# Auxiliary.net
KiCad netlist of a schematic drawn in Altium Designer
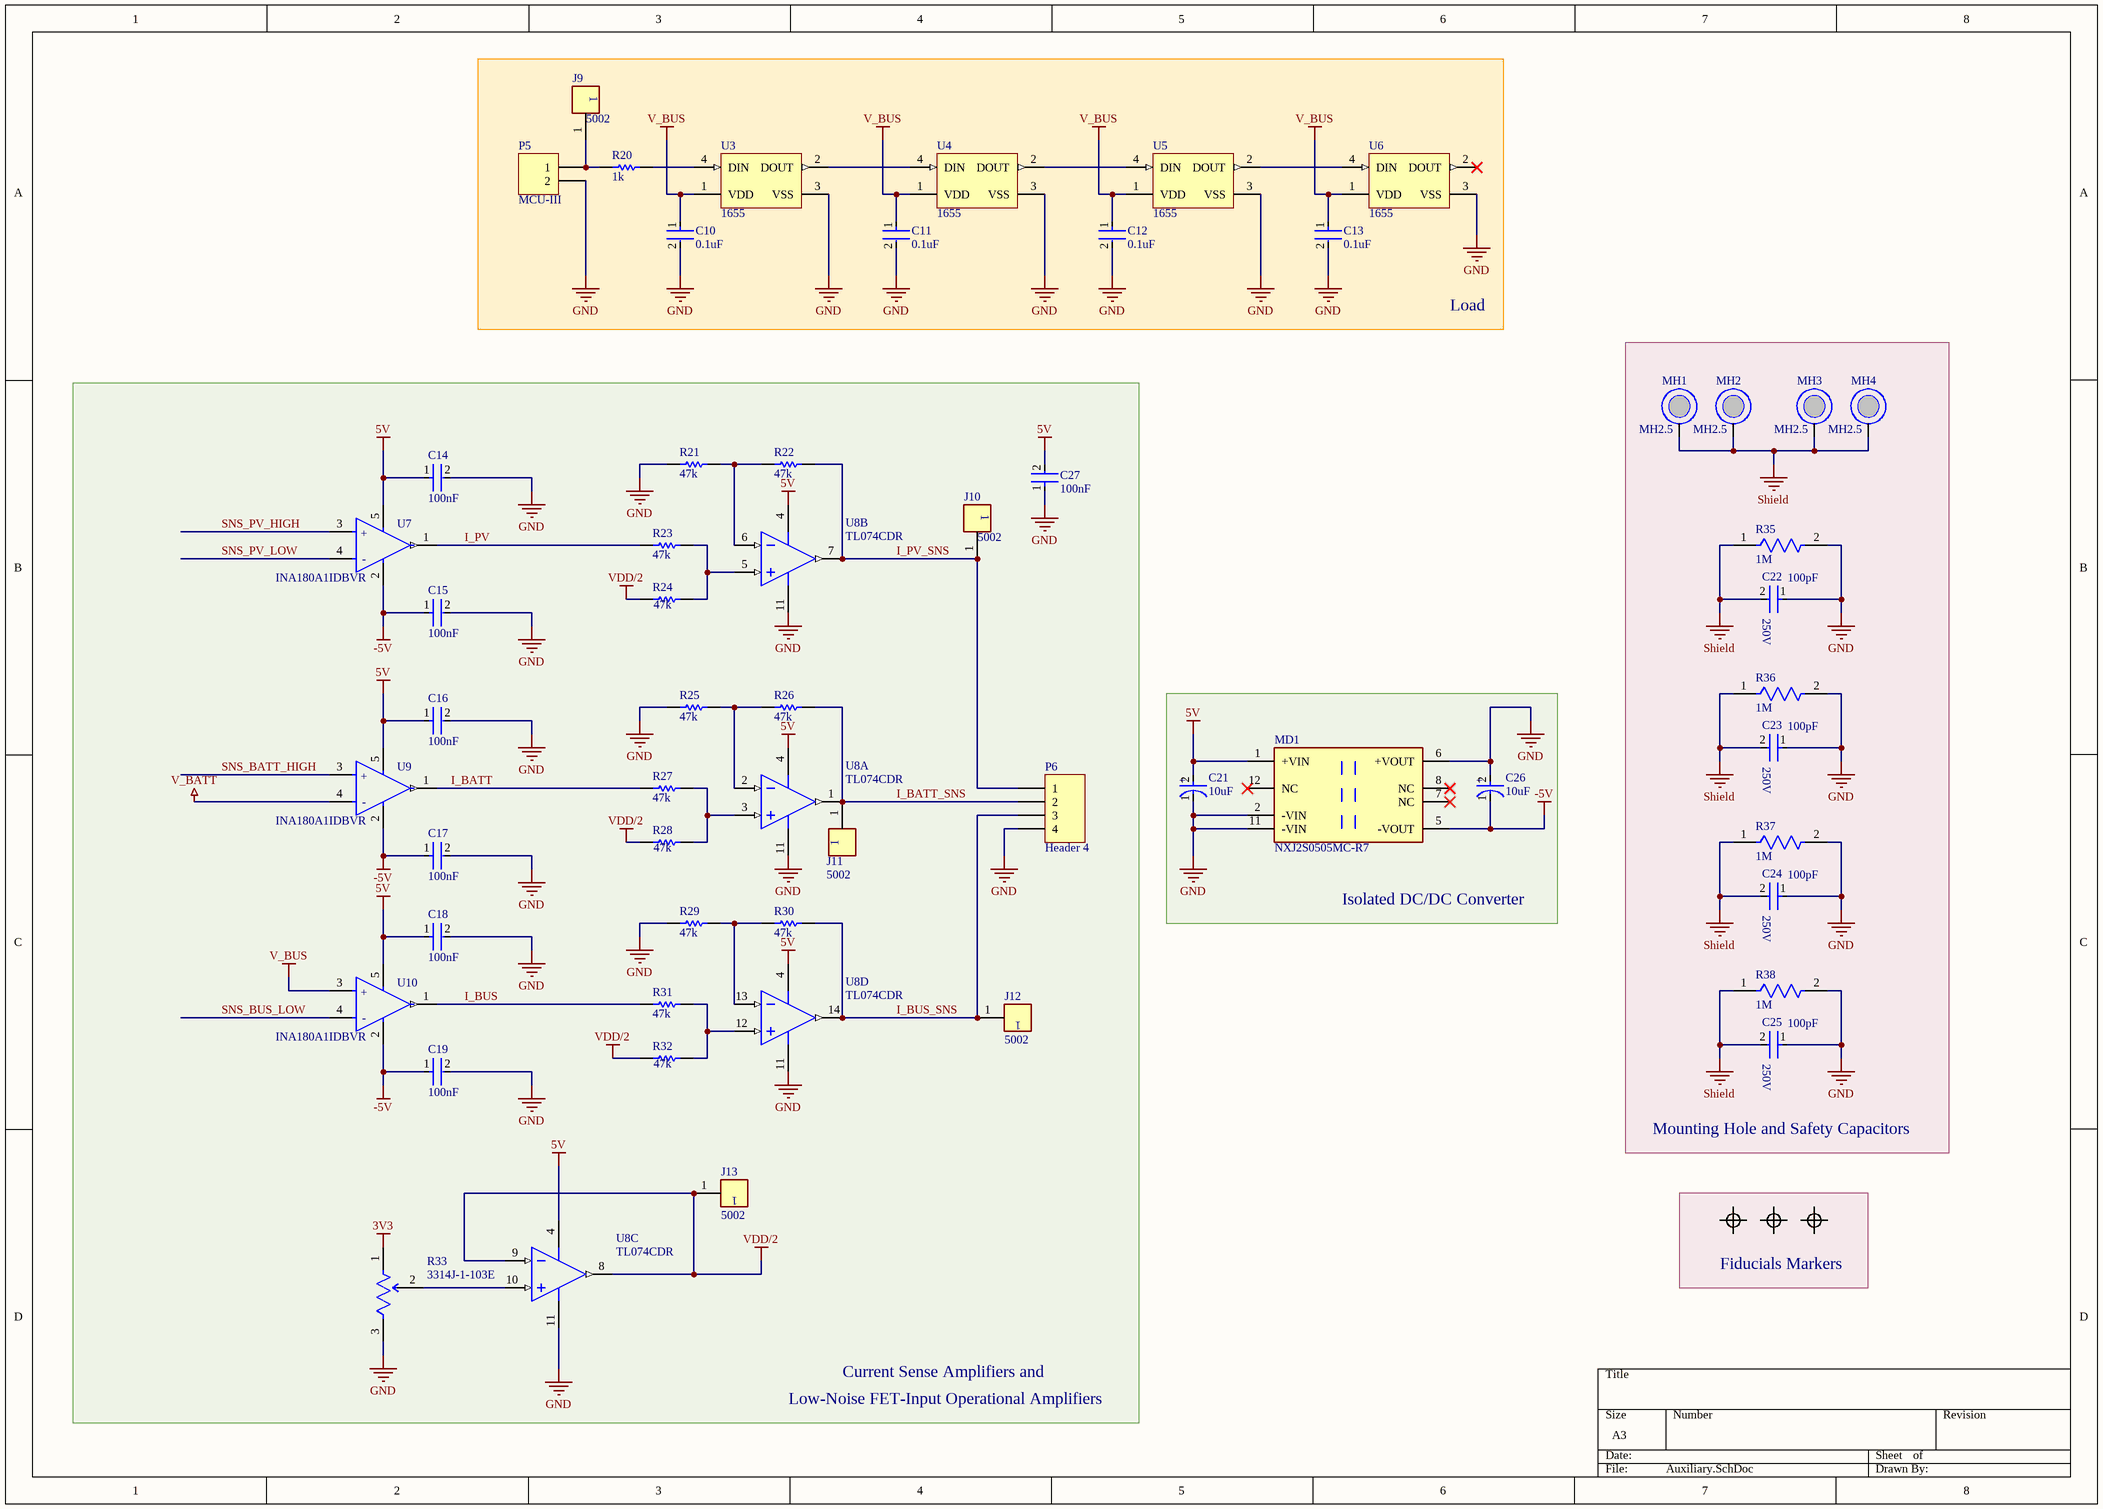
[diagram p0: Auxiliary.SchDoc]

(export (version "E")
  (design (tool "Eeschema 10.0.6"))
  (components
    (comp (ref "C10")
      (value "0.1uF")
      (footprint "FP-GRM155-0_05-MFG")
      (description "CAP CER 0.1UF 16V X7R 0402")
      (fields (field (name "TOLERANCE") "5%") (field (name "VOLTAGE") "16V"))
      (libsource (lib "Altium Content Vault") (part "02cd4be3c70576c341d710602a673aa"))
    )
    (comp (ref "C11")
      (value "0.1uF")
      (footprint "FP-GRM155-0_05-MFG")
      (description "CAP CER 0.1UF 16V X7R 0402")
      (fields (field (name "TOLERANCE") "5%") (field (name "VOLTAGE") "16V"))
      (libsource (lib "Altium Content Vault") (part "02cd4be3c70576c341d710602a673aa"))
    )
    (comp (ref "C12")
      (value "0.1uF")
      (footprint "FP-GRM155-0_05-MFG")
      (description "CAP CER 0.1UF 16V X7R 0402")
      (fields (field (name "TOLERANCE") "5%") (field (name "VOLTAGE") "16V"))
      (libsource (lib "Altium Content Vault") (part "02cd4be3c70576c341d710602a673aa"))
    )
    (comp (ref "C13")
      (value "0.1uF")
      (footprint "FP-GRM155-0_05-MFG")
      (description "CAP CER 0.1UF 16V X7R 0402")
      (fields (field (name "TOLERANCE") "5%") (field (name "VOLTAGE") "16V"))
      (libsource (lib "Altium Content Vault") (part "02cd4be3c70576c341d710602a673aa"))
    )
    (comp (ref "C14")
      (value "100nF")
      (footprint "FP-CGA3E-0_3-0_1-IPC_A")
      (description "Cap Ceramic 100nF 50V X7R 10% Pad SMD 0603 +125°C Automotive T/R")
      (fields (field (name "TOLERANCE") "10%") (field (name "VOLTAGE") "50V"))
      (libsource (lib "Altium Content Vault") (part "b4654b650e69147ec39a6b967a45e02"))
    )
    (comp (ref "C15")
      (value "100nF")
      (footprint "FP-CGA3E-0_3-0_1-IPC_A")
      (description "Cap Ceramic 100nF 50V X7R 10% Pad SMD 0603 +125°C Automotive T/R")
      (fields (field (name "TOLERANCE") "10%") (field (name "VOLTAGE") "50V"))
      (libsource (lib "Altium Content Vault") (part "b4654b650e69147ec39a6b967a45e02"))
    )
    (comp (ref "C16")
      (value "100nF")
      (footprint "FP-CGA3E-0_3-0_1-IPC_A")
      (description "Cap Ceramic 100nF 50V X7R 10% Pad SMD 0603 +125°C Automotive T/R")
      (fields (field (name "TOLERANCE") "10%") (field (name "VOLTAGE") "50V"))
      (libsource (lib "Altium Content Vault") (part "b4654b650e69147ec39a6b967a45e02"))
    )
    (comp (ref "C17")
      (value "100nF")
      (footprint "FP-CGA3E-0_3-0_1-IPC_A")
      (description "Cap Ceramic 100nF 50V X7R 10% Pad SMD 0603 +125°C Automotive T/R")
      (fields (field (name "TOLERANCE") "10%") (field (name "VOLTAGE") "50V"))
      (libsource (lib "Altium Content Vault") (part "b4654b650e69147ec39a6b967a45e02"))
    )
    (comp (ref "C18")
      (value "100nF")
      (footprint "FP-CGA3E-0_3-0_1-IPC_A")
      (description "Cap Ceramic 100nF 50V X7R 10% Pad SMD 0603 +125°C Automotive T/R")
      (fields (field (name "TOLERANCE") "10%") (field (name "VOLTAGE") "50V"))
      (libsource (lib "Altium Content Vault") (part "b4654b650e69147ec39a6b967a45e02"))
    )
    (comp (ref "C19")
      (value "100nF")
      (footprint "FP-CGA3E-0_3-0_1-IPC_A")
      (description "Cap Ceramic 100nF 50V X7R 10% Pad SMD 0603 +125°C Automotive T/R")
      (fields (field (name "TOLERANCE") "10%") (field (name "VOLTAGE") "50V"))
      (libsource (lib "Altium Content Vault") (part "b4654b650e69147ec39a6b967a45e02"))
    )
    (comp (ref "C21")
      (value "10uF")
      (footprint "FP-T491C106K016AT-MFG")
      (description "CAP TANT 10UF 10% 16V 2312")
      (fields (field (name "VOLTAGE") "16V") (field (name "TOLERANCE") "10%"))
      (libsource (lib "Altium Content Vault") (part "a00bbbee19879c290e62620ae7e47b1"))
    )
    (comp (ref "C22")
      (value "100pF")
      (footprint "FP-GA342Q-0_3-e0_3_1_15-IPC_C")
      (description "100pF ±10%  250VAC Ceramic Capacitor X7R 1808 (4520 Metric)")
      (fields (field (name "VOLTAGE") "250V") (field (name "TOLERANCE") "10%"))
      (libsource (lib "Altium Content Vault") (part "ee02319fe6c27a0cbee94bf8aee89f2"))
    )
    (comp (ref "C23")
      (value "100pF")
      (footprint "FP-GA342Q-0_3-e0_3_1_15-IPC_C")
      (description "100pF ±10%  250VAC Ceramic Capacitor X7R 1808 (4520 Metric)")
      (fields (field (name "VOLTAGE") "250V") (field (name "TOLERANCE") "10%"))
      (libsource (lib "Altium Content Vault") (part "ee02319fe6c27a0cbee94bf8aee89f2"))
    )
    (comp (ref "C24")
      (value "100pF")
      (footprint "FP-GA342Q-0_3-e0_3_1_15-IPC_C")
      (description "100pF ±10%  250VAC Ceramic Capacitor X7R 1808 (4520 Metric)")
      (fields (field (name "VOLTAGE") "250V") (field (name "TOLERANCE") "10%"))
      (libsource (lib "Altium Content Vault") (part "ee02319fe6c27a0cbee94bf8aee89f2"))
    )
    (comp (ref "C25")
      (value "100pF")
      (footprint "FP-GA342Q-0_3-e0_3_1_15-IPC_C")
      (description "100pF ±10%  250VAC Ceramic Capacitor X7R 1808 (4520 Metric)")
      (fields (field (name "VOLTAGE") "250V") (field (name "TOLERANCE") "10%"))
      (libsource (lib "Altium Content Vault") (part "ee02319fe6c27a0cbee94bf8aee89f2"))
    )
    (comp (ref "C26")
      (value "10uF")
      (footprint "FP-T491C106K016AT-MFG")
      (description "CAP TANT 10UF 10% 16V 2312")
      (fields (field (name "VOLTAGE") "16V") (field (name "TOLERANCE") "10%"))
      (libsource (lib "Altium Content Vault") (part "a00bbbee19879c290e62620ae7e47b1"))
    )
    (comp (ref "C27")
      (value "100nF")
      (footprint "FP-CGA3E-0_3-0_1-IPC_A")
      (description "Cap Ceramic 100nF 50V X7R 10% Pad SMD 0603 +125°C Automotive T/R")
      (fields (field (name "TOLERANCE") "10%") (field (name "VOLTAGE") "50V"))
      (libsource (lib "Altium Content Vault") (part "b4654b650e69147ec39a6b967a45e02"))
    )
    (comp (ref "F1")
      (value "FIDUCIAL")
      (footprint "FIDUCIAL")
      (libsource (lib "LUCRARE_LICENTA_SCHEMATIC") (part "FIDUCIAL"))
    )
    (comp (ref "F2")
      (value "FIDUCIAL")
      (footprint "FIDUCIAL")
      (libsource (lib "LUCRARE_LICENTA_SCHEMATIC") (part "FIDUCIAL"))
    )
    (comp (ref "F3")
      (value "FIDUCIAL")
      (footprint "FIDUCIAL")
      (libsource (lib "LUCRARE_LICENTA_SCHEMATIC") (part "FIDUCIAL"))
    )
    (comp (ref "J9")
      (value "5002")
      (footprint "FP-5002-MFG")
      (description "PC TEST POINT MINIATURE WHITE")
      (libsource (lib "") (part "1e4615820a309e3ce90f9e6d957b7fa_1"))
    )
    (comp (ref "J10")
      (value "5002")
      (footprint "FP-5002-MFG")
      (description "PC TEST POINT MINIATURE WHITE")
      (libsource (lib "") (part "1e4615820a309e3ce90f9e6d957b7fa_1"))
    )
    (comp (ref "J11")
      (value "5002")
      (footprint "FP-5002-MFG")
      (description "PC TEST POINT MINIATURE WHITE")
      (libsource (lib "") (part "1e4615820a309e3ce90f9e6d957b7fa_2"))
    )
    (comp (ref "J12")
      (value "5002")
      (footprint "FP-5002-MFG")
      (description "PC TEST POINT MINIATURE WHITE")
      (libsource (lib "Altium Content Vault") (part "1e4615820a309e3ce90f9e6d957b7fa"))
    )
    (comp (ref "J13")
      (value "5002")
      (footprint "FP-5002-MFG")
      (description "PC TEST POINT MINIATURE WHITE")
      (libsource (lib "Altium Content Vault") (part "1e4615820a309e3ce90f9e6d957b7fa"))
    )
    (comp (ref "MD1")
      (value "NXJ2S0505MC-R7")
      (footprint "FP-NXJ2SM-MFG")
      (description "DC DC CONVERTER 5V 2W")
      (libsource (lib "Altium Content Vault") (part "702c7546206b672000c29661061961a"))
    )
    (comp (ref "MH1")
      (value "MH2.5")
      (footprint "Mounting Hole")
      (libsource (lib "LUCRARE_LICENTA_SCHEMATIC") (part "Mounting Hole"))
    )
    (comp (ref "MH2")
      (value "MH2.5")
      (footprint "Mounting Hole")
      (libsource (lib "LUCRARE_LICENTA_SCHEMATIC") (part "Mounting Hole"))
    )
    (comp (ref "MH3")
      (value "MH2.5")
      (footprint "Mounting Hole")
      (libsource (lib "LUCRARE_LICENTA_SCHEMATIC") (part "Mounting Hole"))
    )
    (comp (ref "MH4")
      (value "MH2.5")
      (footprint "Mounting Hole")
      (libsource (lib "LUCRARE_LICENTA_SCHEMATIC") (part "Mounting Hole"))
    )
    (comp (ref "P5")
      (value "MCU-III")
      (footprint "HDR1X2")
      (description "Header, 2-Pin")
      (fields (field (name "PUBLISHER") "Altium Limited"))
      (libsource (lib "Miscellaneous Connectors") (part "Header 2"))
    )
    (comp (ref "P6")
      (value "Header 4")
      (footprint "HDR1X4")
      (description "Header, 4-Pin")
      (fields (field (name "PUBLISHER") "Altium Limited"))
      (libsource (lib "Miscellaneous Connectors") (part "Header 4"))
    )
    (comp (ref "R20")
      (value "1k")
      (footprint "RESC1608X55X30LL15T15")
      (fields (field (name "PART NUMBER") "ERJ-3EKF1001V") (field (name "MANUFACTURER") "Panasonic"))
      (libsource (lib "Altium Content Vault") (part "RES"))
    )
    (comp (ref "R21")
      (value "47k")
      (footprint "RESC1608X55X30NL15T15")
      (description "Chip Resistor, 47 KOhm, +/- 1%, 0.1 W, -55 to 155 degC, 0603 (1608 Metric), RoHS, Tape and Reel")
      (libsource (lib "Altium Content Vault") (part "RES-2"))
    )
    (comp (ref "R22")
      (value "47k")
      (footprint "RESC1608X55X30NL15T15")
      (description "Chip Resistor, 47 KOhm, +/- 1%, 0.1 W, -55 to 155 degC, 0603 (1608 Metric), RoHS, Tape and Reel")
      (libsource (lib "Altium Content Vault") (part "RES-2"))
    )
    (comp (ref "R23")
      (value "47k")
      (footprint "RESC1608X55X30NL15T15")
      (description "Chip Resistor, 47 KOhm, +/- 1%, 0.1 W, -55 to 155 degC, 0603 (1608 Metric), RoHS, Tape and Reel")
      (libsource (lib "Altium Content Vault") (part "RES-2"))
    )
    (comp (ref "R24")
      (value "47k")
      (footprint "RESC1608X55X30NL15T15")
      (description "Chip Resistor, 47 KOhm, +/- 1%, 0.1 W, -55 to 155 degC, 0603 (1608 Metric), RoHS, Tape and Reel")
      (libsource (lib "Altium Content Vault") (part "RES-2"))
    )
    (comp (ref "R25")
      (value "47k")
      (footprint "RESC1608X55X30NL15T15")
      (description "Chip Resistor, 47 KOhm, +/- 1%, 0.1 W, -55 to 155 degC, 0603 (1608 Metric), RoHS, Tape and Reel")
      (libsource (lib "Altium Content Vault") (part "RES-2"))
    )
    (comp (ref "R26")
      (value "47k")
      (footprint "RESC1608X55X30NL15T15")
      (description "Chip Resistor, 47 KOhm, +/- 1%, 0.1 W, -55 to 155 degC, 0603 (1608 Metric), RoHS, Tape and Reel")
      (libsource (lib "Altium Content Vault") (part "RES-2"))
    )
    (comp (ref "R27")
      (value "47k")
      (footprint "RESC1608X55X30NL15T15")
      (description "Chip Resistor, 47 KOhm, +/- 1%, 0.1 W, -55 to 155 degC, 0603 (1608 Metric), RoHS, Tape and Reel")
      (libsource (lib "Altium Content Vault") (part "RES-2"))
    )
    (comp (ref "R28")
      (value "47k")
      (footprint "RESC1608X55X30NL15T15")
      (description "Chip Resistor, 47 KOhm, +/- 1%, 0.1 W, -55 to 155 degC, 0603 (1608 Metric), RoHS, Tape and Reel")
      (libsource (lib "Altium Content Vault") (part "RES-2"))
    )
    (comp (ref "R29")
      (value "47k")
      (footprint "RESC1608X55X30NL15T15")
      (description "Chip Resistor, 47 KOhm, +/- 1%, 0.1 W, -55 to 155 degC, 0603 (1608 Metric), RoHS, Tape and Reel")
      (libsource (lib "Altium Content Vault") (part "RES-2"))
    )
    (comp (ref "R30")
      (value "47k")
      (footprint "RESC1608X55X30NL15T15")
      (description "Chip Resistor, 47 KOhm, +/- 1%, 0.1 W, -55 to 155 degC, 0603 (1608 Metric), RoHS, Tape and Reel")
      (libsource (lib "Altium Content Vault") (part "RES-2"))
    )
    (comp (ref "R31")
      (value "47k")
      (footprint "RESC1608X55X30NL15T15")
      (description "Chip Resistor, 47 KOhm, +/- 1%, 0.1 W, -55 to 155 degC, 0603 (1608 Metric), RoHS, Tape and Reel")
      (libsource (lib "Altium Content Vault") (part "RES-2"))
    )
    (comp (ref "R32")
      (value "47k")
      (footprint "RESC1608X55X30NL15T15")
      (description "Chip Resistor, 47 KOhm, +/- 1%, 0.1 W, -55 to 155 degC, 0603 (1608 Metric), RoHS, Tape and Reel")
      (libsource (lib "Altium Content Vault") (part "RES-2"))
    )
    (comp (ref "R33")
      (value "3314J-1-103E")
      (footprint "FP-3314J-1-MFG")
      (description "TRIMMER 10K OHM 0.25W J LEAD TOP")
      (libsource (lib "Altium Content Vault") (part "13357d81287629c2fd191d242cfa50c"))
    )
    (comp (ref "R35")
      (value "1M")
      (footprint "FP-CRCW0603C-e3-MFG")
      (description "RES 1M OHM 1% 1/10W 0603")
      (fields (field (name "TOLERANCE") "1%"))
      (libsource (lib "Altium Content Vault") (part "1029c3af85768c4190bb7ad29bc67b5"))
    )
    (comp (ref "R36")
      (value "1M")
      (footprint "FP-CRCW0603C-e3-MFG")
      (description "RES 1M OHM 1% 1/10W 0603")
      (fields (field (name "TOLERANCE") "1%"))
      (libsource (lib "Altium Content Vault") (part "1029c3af85768c4190bb7ad29bc67b5"))
    )
    (comp (ref "R37")
      (value "1M")
      (footprint "FP-CRCW0603C-e3-MFG")
      (description "RES 1M OHM 1% 1/10W 0603")
      (fields (field (name "TOLERANCE") "1%"))
      (libsource (lib "Altium Content Vault") (part "1029c3af85768c4190bb7ad29bc67b5"))
    )
    (comp (ref "R38")
      (value "1M")
      (footprint "FP-CRCW0603C-e3-MFG")
      (description "RES 1M OHM 1% 1/10W 0603")
      (fields (field (name "TOLERANCE") "1%"))
      (libsource (lib "Altium Content Vault") (part "1029c3af85768c4190bb7ad29bc67b5"))
    )
    (comp (ref "U3")
      (value "1655")
      (footprint "ADA-RGB-1655_V")
      (fields (field (name "MANUFACTURER") "Adafruit-Industries-LLC"))
      (libsource (lib "Altium Content Vault") (part "ADA-RGB-1655-4"))
    )
    (comp (ref "U4")
      (value "1655")
      (footprint "ADA-RGB-1655_V")
      (fields (field (name "MANUFACTURER") "Adafruit-Industries-LLC"))
      (libsource (lib "Altium Content Vault") (part "ADA-RGB-1655-4"))
    )
    (comp (ref "U5")
      (value "1655")
      (footprint "ADA-RGB-1655_V")
      (fields (field (name "MANUFACTURER") "Adafruit-Industries-LLC"))
      (libsource (lib "Altium Content Vault") (part "ADA-RGB-1655-4"))
    )
    (comp (ref "U6")
      (value "1655")
      (footprint "ADA-RGB-1655_V")
      (fields (field (name "MANUFACTURER") "Adafruit-Industries-LLC"))
      (libsource (lib "Altium Content Vault") (part "ADA-RGB-1655-4"))
    )
    (comp (ref "U7")
      (value "INA180A1IDBVR")
      (footprint "FP-DBV0005A-IPC_A")
      (description "IC CURR SENSE 1 CIRCUIT SOT23-5")
      (libsource (lib "Altium Content Vault") (part "0a55cf1a948ad01a3239aec1b7efad0"))
    )
    (comp (ref "U8")
      (value "TL074CDR")
      (footprint "D0014A_N")
      (fields (field (name "MANUFACTURER") "Texas Instruments"))
      (libsource (lib "Altium Content Vault") (part "TI-TLXX4X_MC3403-X14"))
    )
    (comp (ref "U9")
      (value "INA180A1IDBVR")
      (footprint "FP-DBV0005A-IPC_A")
      (description "IC CURR SENSE 1 CIRCUIT SOT23-5")
      (libsource (lib "Altium Content Vault") (part "0a55cf1a948ad01a3239aec1b7efad0"))
    )
    (comp (ref "U10")
      (value "INA180A1IDBVR")
      (footprint "FP-DBV0005A-IPC_A")
      (description "IC CURR SENSE 1 CIRCUIT SOT23-5")
      (libsource (lib "Altium Content Vault") (part "0a55cf1a948ad01a3239aec1b7efad0"))
    )
  )
  (nets
    (net (code "1") (name "-5V") (class "Default")
      (node (ref "C15") (pin "1") (pinfunction "1_1") (pintype "passive"))
      (node (ref "C17") (pin "1") (pinfunction "1_1") (pintype "passive"))
      (node (ref "C19") (pin "1") (pinfunction "1_1") (pintype "passive"))
      (node (ref "C26") (pin "1") (pinfunction "C_1") (pintype "passive"))
      (node (ref "MD1") (pin "5") (pinfunction "-VOUT_5") (pintype "power_in"))
      (node (ref "U10") (pin "2") (pinfunction "GND_2") (pintype "power_in"))
      (node (ref "U7") (pin "2") (pinfunction "GND_2") (pintype "power_in"))
      (node (ref "U9") (pin "2") (pinfunction "GND_2") (pintype "power_in"))
    )
    (net (code "2") (name "/I_BATT") (class "Default")
      (node (ref "R27") (pin "2") (pinfunction "2_2") (pintype "passive"))
      (node (ref "U9") (pin "1") (pinfunction "OUT_1") (pintype "output"))
    )
    (net (code "3") (name "/I_BATT_SNS") (class "Default")
      (node (ref "J11") (pin "1") (pinfunction "1_1") (pintype "passive"))
      (node (ref "P6") (pin "2") (pinfunction "2_2") (pintype "passive"))
      (node (ref "R26") (pin "1") (pinfunction "1_1") (pintype "passive"))
      (node (ref "U8") (pin "1") (pinfunction "OUT1_1") (pintype "output"))
    )
    (net (code "4") (name "/I_BUS") (class "Default")
      (node (ref "R31") (pin "2") (pinfunction "2_2") (pintype "passive"))
      (node (ref "U10") (pin "1") (pinfunction "OUT_1") (pintype "output"))
    )
    (net (code "5") (name "/I_BUS_SNS") (class "Default")
      (node (ref "J12") (pin "1") (pinfunction "1_1") (pintype "passive"))
      (node (ref "P6") (pin "3") (pinfunction "3_3") (pintype "passive"))
      (node (ref "R30") (pin "1") (pinfunction "1_1") (pintype "passive"))
      (node (ref "U8") (pin "14") (pinfunction "OUT4_14") (pintype "output"))
    )
    (net (code "6") (name "/I_PV") (class "Default")
      (node (ref "R23") (pin "2") (pinfunction "2_2") (pintype "passive"))
      (node (ref "U7") (pin "1") (pinfunction "OUT_1") (pintype "output"))
    )
    (net (code "7") (name "/I_PV_SNS") (class "Default")
      (node (ref "J10") (pin "1") (pinfunction "1_1") (pintype "passive"))
      (node (ref "P6") (pin "1") (pinfunction "1_1") (pintype "passive"))
      (node (ref "R22") (pin "1") (pinfunction "1_1") (pintype "passive"))
      (node (ref "U8") (pin "7") (pinfunction "OUT2_7") (pintype "output"))
    )
    (net (code "8") (name "/SNS_BATT_HIGH") (class "Default")
      (node (ref "U9") (pin "3") (pinfunction "IN+_3") (pintype "tri_state"))
    )
    (net (code "9") (name "/SNS_BUS_LOW") (class "Default")
      (node (ref "U10") (pin "4") (pinfunction "IN-_4") (pintype "tri_state"))
    )
    (net (code "10") (name "/SNS_PV_HIGH") (class "Default")
      (node (ref "U7") (pin "3") (pinfunction "IN+_3") (pintype "tri_state"))
    )
    (net (code "11") (name "/SNS_PV_LOW") (class "Default")
      (node (ref "U7") (pin "4") (pinfunction "IN-_4") (pintype "tri_state"))
    )
    (net (code "12") (name "3V3") (class "Default")
      (node (ref "R33") (pin "1") (pinfunction "CCW_1") (pintype "passive"))
    )
    (net (code "13") (name "5V") (class "Default")
      (node (ref "C14") (pin "1") (pinfunction "1_1") (pintype "passive"))
      (node (ref "C16") (pin "1") (pinfunction "1_1") (pintype "passive"))
      (node (ref "C18") (pin "1") (pinfunction "1_1") (pintype "passive"))
      (node (ref "C21") (pin "2") (pinfunction "A_2") (pintype "passive"))
      (node (ref "C27") (pin "2") (pinfunction "2_2") (pintype "passive"))
      (node (ref "MD1") (pin "1") (pinfunction "+VIN_1") (pintype "power_in"))
      (node (ref "U10") (pin "5") (pinfunction "VS_5") (pintype "power_in"))
      (node (ref "U7") (pin "5") (pinfunction "VS_5") (pintype "power_in"))
      (node (ref "U8") (pin "4") (pinfunction "VCC+_4") (pintype "power_in"))
      (node (ref "U9") (pin "5") (pinfunction "VS_5") (pintype "power_in"))
    )
    (net (code "14") (name "GND") (class "Default")
      (node (ref "C10") (pin "2") (pinfunction "2_2") (pintype "passive"))
      (node (ref "C11") (pin "2") (pinfunction "2_2") (pintype "passive"))
      (node (ref "C12") (pin "2") (pinfunction "2_2") (pintype "passive"))
      (node (ref "C13") (pin "2") (pinfunction "2_2") (pintype "passive"))
      (node (ref "C14") (pin "2") (pinfunction "2_2") (pintype "passive"))
      (node (ref "C15") (pin "2") (pinfunction "2_2") (pintype "passive"))
      (node (ref "C16") (pin "2") (pinfunction "2_2") (pintype "passive"))
      (node (ref "C17") (pin "2") (pinfunction "2_2") (pintype "passive"))
      (node (ref "C18") (pin "2") (pinfunction "2_2") (pintype "passive"))
      (node (ref "C19") (pin "2") (pinfunction "2_2") (pintype "passive"))
      (node (ref "C21") (pin "1") (pinfunction "C_1") (pintype "passive"))
      (node (ref "C22") (pin "1") (pinfunction "1_1") (pintype "passive"))
      (node (ref "C23") (pin "1") (pinfunction "1_1") (pintype "passive"))
      (node (ref "C24") (pin "1") (pinfunction "1_1") (pintype "passive"))
      (node (ref "C25") (pin "1") (pinfunction "1_1") (pintype "passive"))
      (node (ref "C26") (pin "2") (pinfunction "A_2") (pintype "passive"))
      (node (ref "C27") (pin "1") (pinfunction "1_1") (pintype "passive"))
      (node (ref "MD1") (pin "11") (pinfunction "-VIN_11") (pintype "power_in"))
      (node (ref "MD1") (pin "2") (pinfunction "-VIN_2") (pintype "power_in"))
      (node (ref "MD1") (pin "6") (pinfunction "+VOUT_6") (pintype "power_in"))
      (node (ref "P5") (pin "2") (pinfunction "2_2") (pintype "passive"))
      (node (ref "P6") (pin "4") (pinfunction "4_4") (pintype "passive"))
      (node (ref "R21") (pin "2") (pinfunction "2_2") (pintype "passive"))
      (node (ref "R25") (pin "2") (pinfunction "2_2") (pintype "passive"))
      (node (ref "R29") (pin "2") (pinfunction "2_2") (pintype "passive"))
      (node (ref "R33") (pin "3") (pinfunction "CW_3") (pintype "passive"))
      (node (ref "R35") (pin "2") (pinfunction "2_2") (pintype "passive"))
      (node (ref "R36") (pin "2") (pinfunction "2_2") (pintype "passive"))
      (node (ref "R37") (pin "2") (pinfunction "2_2") (pintype "passive"))
      (node (ref "R38") (pin "2") (pinfunction "2_2") (pintype "passive"))
      (node (ref "U3") (pin "3") (pinfunction "VSS_3") (pintype "power_in"))
      (node (ref "U4") (pin "3") (pinfunction "VSS_3") (pintype "power_in"))
      (node (ref "U5") (pin "3") (pinfunction "VSS_3") (pintype "power_in"))
      (node (ref "U6") (pin "3") (pinfunction "VSS_3") (pintype "power_in"))
      (node (ref "U8") (pin "11") (pinfunction "VCC-_11") (pintype "power_in"))
    )
    (net (code "15") (name "Net-(J9-Pad1)") (class "Default")
      (node (ref "J9") (pin "1") (pinfunction "1_1") (pintype "passive"))
      (node (ref "P5") (pin "1") (pinfunction "1_1") (pintype "passive"))
      (node (ref "R20") (pin "2") (pinfunction "2_2") (pintype "passive"))
    )
    (net (code "16") (name "Net-(R33-WIPER)") (class "Default")
      (node (ref "R33") (pin "2") (pinfunction "WIPER_2") (pintype "passive"))
      (node (ref "U8") (pin "10") (pinfunction "IN3+_10") (pintype "input"))
    )
    (net (code "17") (name "Net-(U3-DIN)") (class "Default")
      (node (ref "R20") (pin "1") (pinfunction "1_1") (pintype "passive"))
      (node (ref "U3") (pin "4") (pinfunction "DIN_4") (pintype "input"))
    )
    (net (code "18") (name "Net-(U3-DOUT)") (class "Default")
      (node (ref "U3") (pin "2") (pinfunction "DOUT_2") (pintype "output"))
      (node (ref "U4") (pin "4") (pinfunction "DIN_4") (pintype "input"))
    )
    (net (code "19") (name "Net-(U4-DOUT)") (class "Default")
      (node (ref "U4") (pin "2") (pinfunction "DOUT_2") (pintype "output"))
      (node (ref "U5") (pin "4") (pinfunction "DIN_4") (pintype "input"))
    )
    (net (code "20") (name "Net-(U5-DOUT)") (class "Default")
      (node (ref "U5") (pin "2") (pinfunction "DOUT_2") (pintype "output"))
      (node (ref "U6") (pin "4") (pinfunction "DIN_4") (pintype "input"))
    )
    (net (code "21") (name "Net-(U8A-IN1+)") (class "Default")
      (node (ref "R27") (pin "1") (pinfunction "1_1") (pintype "passive"))
      (node (ref "R28") (pin "1") (pinfunction "1_1") (pintype "passive"))
      (node (ref "U8") (pin "3") (pinfunction "IN1+_3") (pintype "input"))
    )
    (net (code "22") (name "Net-(U8A-IN1-)") (class "Default")
      (node (ref "R25") (pin "1") (pinfunction "1_1") (pintype "passive"))
      (node (ref "R26") (pin "2") (pinfunction "2_2") (pintype "passive"))
      (node (ref "U8") (pin "2") (pinfunction "IN1-_2") (pintype "input"))
    )
    (net (code "23") (name "Net-(U8B-IN2+)") (class "Default")
      (node (ref "R23") (pin "1") (pinfunction "1_1") (pintype "passive"))
      (node (ref "R24") (pin "1") (pinfunction "1_1") (pintype "passive"))
      (node (ref "U8") (pin "5") (pinfunction "IN2+_5") (pintype "input"))
    )
    (net (code "24") (name "Net-(U8B-IN2-)") (class "Default")
      (node (ref "R21") (pin "1") (pinfunction "1_1") (pintype "passive"))
      (node (ref "R22") (pin "2") (pinfunction "2_2") (pintype "passive"))
      (node (ref "U8") (pin "6") (pinfunction "IN2-_6") (pintype "input"))
    )
    (net (code "25") (name "Net-(U8D-IN4+)") (class "Default")
      (node (ref "R31") (pin "1") (pinfunction "1_1") (pintype "passive"))
      (node (ref "R32") (pin "1") (pinfunction "1_1") (pintype "passive"))
      (node (ref "U8") (pin "12") (pinfunction "IN4+_12") (pintype "input"))
    )
    (net (code "26") (name "Net-(U8D-IN4-)") (class "Default")
      (node (ref "R29") (pin "1") (pinfunction "1_1") (pintype "passive"))
      (node (ref "R30") (pin "2") (pinfunction "2_2") (pintype "passive"))
      (node (ref "U8") (pin "13") (pinfunction "IN4-_13") (pintype "input"))
    )
    (net (code "27") (name "Shield") (class "Default")
      (node (ref "C22") (pin "2") (pinfunction "2_2") (pintype "passive"))
      (node (ref "C23") (pin "2") (pinfunction "2_2") (pintype "passive"))
      (node (ref "C24") (pin "2") (pinfunction "2_2") (pintype "passive"))
      (node (ref "C25") (pin "2") (pinfunction "2_2") (pintype "passive"))
      (node (ref "MH1") (pin "1") (pinfunction "1_1") (pintype "passive"))
      (node (ref "MH2") (pin "1") (pinfunction "1_1") (pintype "passive"))
      (node (ref "MH3") (pin "1") (pinfunction "1_1") (pintype "passive"))
      (node (ref "MH4") (pin "1") (pinfunction "1_1") (pintype "passive"))
      (node (ref "R35") (pin "1") (pinfunction "1_1") (pintype "passive"))
      (node (ref "R36") (pin "1") (pinfunction "1_1") (pintype "passive"))
      (node (ref "R37") (pin "1") (pinfunction "1_1") (pintype "passive"))
      (node (ref "R38") (pin "1") (pinfunction "1_1") (pintype "passive"))
    )
    (net (code "28") (name "VDD{slash}2") (class "Default")
      (node (ref "J13") (pin "1") (pinfunction "1_1") (pintype "passive"))
      (node (ref "R24") (pin "2") (pinfunction "2_2") (pintype "passive"))
      (node (ref "R28") (pin "2") (pinfunction "2_2") (pintype "passive"))
      (node (ref "R32") (pin "2") (pinfunction "2_2") (pintype "passive"))
      (node (ref "U8") (pin "8") (pinfunction "OUT3_8") (pintype "output"))
      (node (ref "U8") (pin "9") (pinfunction "IN3-_9") (pintype "input"))
    )
    (net (code "29") (name "V_BATT") (class "Default")
      (node (ref "U9") (pin "4") (pinfunction "IN-_4") (pintype "tri_state"))
    )
    (net (code "30") (name "V_BUS") (class "Default")
      (node (ref "C10") (pin "1") (pinfunction "1_1") (pintype "passive"))
      (node (ref "C11") (pin "1") (pinfunction "1_1") (pintype "passive"))
      (node (ref "C12") (pin "1") (pinfunction "1_1") (pintype "passive"))
      (node (ref "C13") (pin "1") (pinfunction "1_1") (pintype "passive"))
      (node (ref "U10") (pin "3") (pinfunction "IN+_3") (pintype "tri_state"))
      (node (ref "U3") (pin "1") (pinfunction "VDD_1") (pintype "power_in"))
      (node (ref "U4") (pin "1") (pinfunction "VDD_1") (pintype "power_in"))
      (node (ref "U5") (pin "1") (pinfunction "VDD_1") (pintype "power_in"))
      (node (ref "U6") (pin "1") (pinfunction "VDD_1") (pintype "power_in"))
    )
    (net (code "31") (name "unconnected-(MD1-NC-Pad7)") (class "Default")
      (node (ref "MD1") (pin "7") (pinfunction "NC_7") (pintype "passive+no_connect"))
    )
    (net (code "32") (name "unconnected-(MD1-NC-Pad8)") (class "Default")
      (node (ref "MD1") (pin "8") (pinfunction "NC_8") (pintype "passive+no_connect"))
    )
    (net (code "33") (name "unconnected-(MD1-NC-Pad12)") (class "Default")
      (node (ref "MD1") (pin "12") (pinfunction "NC_12") (pintype "passive+no_connect"))
    )
    (net (code "34") (name "unconnected-(U6-DOUT-Pad2)") (class "Default")
      (node (ref "U6") (pin "2") (pinfunction "DOUT_2") (pintype "output+no_connect"))
    )
  )
)
